# B7_OpenCR_PCB_Shield.net
KiCad netlist of a schematic drawn in EAGLE
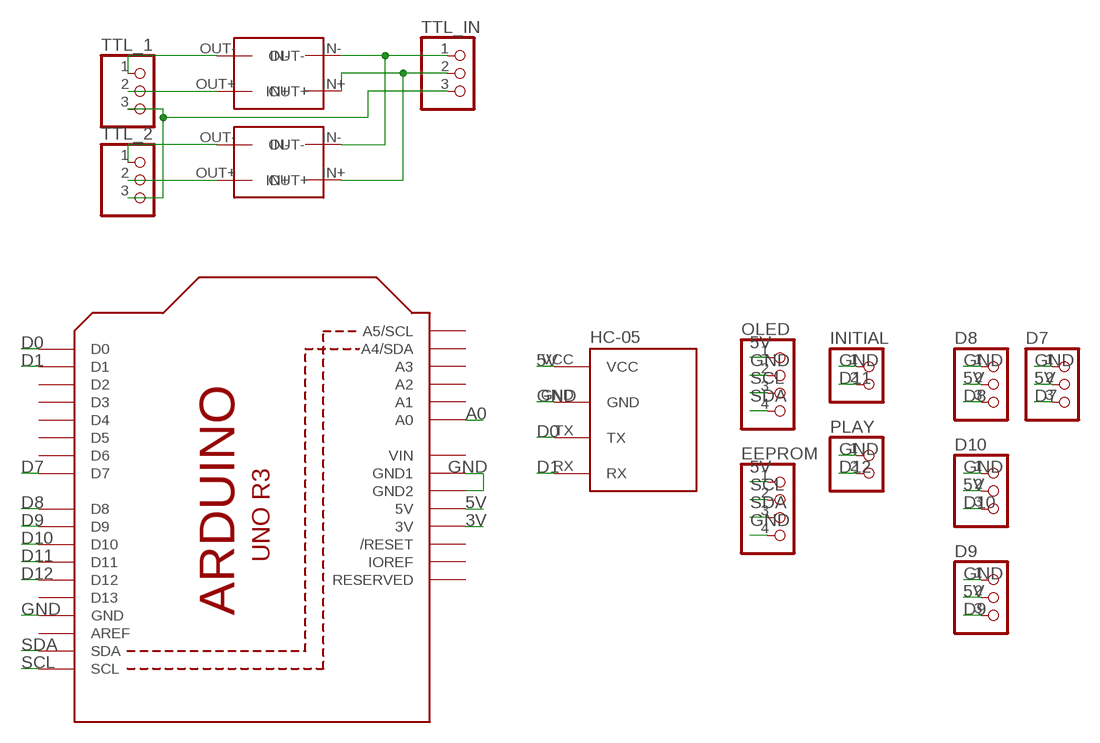
[diagram p0: schematic, sheet 1]

(export (version "E")
  (design (tool "Eeschema 10.0.6"))
  (components
    (comp (ref "D7")
      (value "PINHD-1X3")
      (footprint "eagle-import:1X03")
      (libsource (lib "eagle-import") (part "PINHD-1X3"))
    )
    (comp (ref "D8")
      (value "PINHD-1X3")
      (footprint "eagle-import:1X03")
      (libsource (lib "eagle-import") (part "PINHD-1X3"))
    )
    (comp (ref "D9")
      (value "PINHD-1X3")
      (footprint "eagle-import:1X03")
      (libsource (lib "eagle-import") (part "PINHD-1X3"))
    )
    (comp (ref "D10")
      (value "PINHD-1X3")
      (footprint "eagle-import:1X03")
      (libsource (lib "eagle-import") (part "PINHD-1X3"))
    )
    (comp (ref "EEPROM")
      (value "PINHD-1X4")
      (footprint "eagle-import:1X04")
      (libsource (lib "eagle-import") (part "PINHD-1X4"))
    )
    (comp (ref "HC-05")
      (value "BLUETOOTH_BOARD")
      (footprint "eagle-import:BT_BOARD_FOOTPRINT")
      (libsource (lib "eagle-import") (part "BLUETOOTH_BOARD"))
    )
    (comp (ref "INITIAL")
      (value "PINHD-1X2")
      (footprint "eagle-import:1X02")
      (libsource (lib "eagle-import") (part "PINHD-1X2"))
    )
    (comp (ref "OLED")
      (value "PINHD-1X4")
      (footprint "eagle-import:1X04")
      (libsource (lib "eagle-import") (part "PINHD-1X4"))
    )
    (comp (ref "PLAY")
      (value "PINHD-1X2")
      (footprint "eagle-import:1X02")
      (libsource (lib "eagle-import") (part "PINHD-1X2"))
    )
    (comp (ref "TTL_1")
      (value "PINHD-1X3")
      (footprint "eagle-import:1X03")
      (libsource (lib "eagle-import") (part "PINHD-1X3"))
    )
    (comp (ref "TTL_2")
      (value "PINHD-1X3")
      (footprint "eagle-import:1X03")
      (libsource (lib "eagle-import") (part "PINHD-1X3"))
    )
    (comp (ref "TTL_IN")
      (value "PINHD-1X3")
      (footprint "eagle-import:1X03")
      (libsource (lib "eagle-import") (part "PINHD-1X3"))
    )
    (comp (ref "U$1")
      (value "LM2596LM2596")
      (footprint "eagle-import:LM2596")
      (libsource (lib "eagle-import") (part "LM2596LM2596"))
    )
    (comp (ref "U$2")
      (value "LM2596LM2596")
      (footprint "eagle-import:LM2596")
      (libsource (lib "eagle-import") (part "LM2596LM2596"))
    )
    (comp (ref "U2")
      (value "ARDUINOR3-BPLACE")
      (footprint "eagle-import:ARDUINOR3-BPLACE")
      (libsource (lib "eagle-import") (part "ARDUINOR3-BPLACE"))
    )
  )
  (nets
    (net (code "1") (name "/3V") (class "Default")
      (node (ref "U2") (pin "3V") (pinfunction "3V_3V") (pintype "power_in"))
    )
    (net (code "2") (name "/5V") (class "Default")
      (node (ref "D10") (pin "2") (pinfunction "2_2") (pintype "passive"))
      (node (ref "D7") (pin "2") (pinfunction "2_2") (pintype "passive"))
      (node (ref "D8") (pin "2") (pinfunction "2_2") (pintype "passive"))
      (node (ref "D9") (pin "2") (pinfunction "2_2") (pintype "passive"))
      (node (ref "EEPROM") (pin "1") (pinfunction "1_1") (pintype "passive"))
      (node (ref "HC-05") (pin "VCC") (pinfunction "VCC_VCC") (pintype "bidirectional"))
      (node (ref "OLED") (pin "1") (pinfunction "1_1") (pintype "passive"))
      (node (ref "U2") (pin "5V") (pinfunction "5V_5V") (pintype "power_in"))
    )
    (net (code "3") (name "/A0") (class "Default")
      (node (ref "U2") (pin "A0") (pinfunction "A0_A0") (pintype "bidirectional"))
    )
    (net (code "4") (name "/D0") (class "Default")
      (node (ref "HC-05") (pin "TX") (pinfunction "TX_TX") (pintype "bidirectional"))
      (node (ref "U2") (pin "D0") (pinfunction "D0_D0") (pintype "bidirectional"))
    )
    (net (code "5") (name "/D1") (class "Default")
      (node (ref "HC-05") (pin "RX") (pinfunction "RX_RX") (pintype "bidirectional"))
      (node (ref "U2") (pin "D1") (pinfunction "D1_D1") (pintype "bidirectional"))
    )
    (net (code "6") (name "/D7") (class "Default")
      (node (ref "D7") (pin "3") (pinfunction "3_3") (pintype "passive"))
      (node (ref "U2") (pin "D7") (pinfunction "D7_D7") (pintype "bidirectional"))
    )
    (net (code "7") (name "/D8") (class "Default")
      (node (ref "D8") (pin "3") (pinfunction "3_3") (pintype "passive"))
      (node (ref "U2") (pin "D8") (pinfunction "D8_D8") (pintype "bidirectional"))
    )
    (net (code "8") (name "/D9") (class "Default")
      (node (ref "D9") (pin "3") (pinfunction "3_3") (pintype "passive"))
      (node (ref "U2") (pin "D9") (pinfunction "D9_D9") (pintype "bidirectional"))
    )
    (net (code "9") (name "/D10") (class "Default")
      (node (ref "D10") (pin "3") (pinfunction "3_3") (pintype "passive"))
      (node (ref "U2") (pin "D10") (pinfunction "D10_D10") (pintype "bidirectional"))
    )
    (net (code "10") (name "/D11") (class "Default")
      (node (ref "INITIAL") (pin "2") (pinfunction "2_2") (pintype "passive"))
      (node (ref "U2") (pin "D11") (pinfunction "D11_D11") (pintype "bidirectional"))
    )
    (net (code "11") (name "/D12") (class "Default")
      (node (ref "PLAY") (pin "2") (pinfunction "2_2") (pintype "passive"))
      (node (ref "U2") (pin "D12") (pinfunction "D12_D12") (pintype "bidirectional"))
    )
    (net (code "12") (name "/GND") (class "Default")
      (node (ref "D10") (pin "1") (pinfunction "1_1") (pintype "passive"))
      (node (ref "D7") (pin "1") (pinfunction "1_1") (pintype "passive"))
      (node (ref "D8") (pin "1") (pinfunction "1_1") (pintype "passive"))
      (node (ref "D9") (pin "1") (pinfunction "1_1") (pintype "passive"))
      (node (ref "EEPROM") (pin "4") (pinfunction "4_4") (pintype "passive"))
      (node (ref "HC-05") (pin "GND") (pinfunction "GND_GND") (pintype "bidirectional"))
      (node (ref "INITIAL") (pin "1") (pinfunction "1_1") (pintype "passive"))
      (node (ref "OLED") (pin "2") (pinfunction "2_2") (pintype "passive"))
      (node (ref "PLAY") (pin "1") (pinfunction "1_1") (pintype "passive"))
      (node (ref "U2") (pin "GND") (pinfunction "GND_GND") (pintype "power_in"))
      (node (ref "U2") (pin "GND1") (pinfunction "GND1_GND1") (pintype "power_in"))
      (node (ref "U2") (pin "GND2") (pinfunction "GND2_GND2") (pintype "power_in"))
    )
    (net (code "13") (name "/SCL") (class "Default")
      (node (ref "EEPROM") (pin "2") (pinfunction "2_2") (pintype "passive"))
      (node (ref "OLED") (pin "3") (pinfunction "3_3") (pintype "passive"))
      (node (ref "U2") (pin "SCL") (pinfunction "SCL_SCL") (pintype "bidirectional"))
    )
    (net (code "14") (name "/SDA") (class "Default")
      (node (ref "EEPROM") (pin "3") (pinfunction "3_3") (pintype "passive"))
      (node (ref "OLED") (pin "4") (pinfunction "4_4") (pintype "passive"))
      (node (ref "U2") (pin "SDA") (pinfunction "SDA_SDA") (pintype "bidirectional"))
    )
    (net (code "15") (name "/VIN") (class "Default")
      (node (ref "U2") (pin "VIN") (pinfunction "VIN_VIN") (pintype "power_in"))
    )
    (net (code "16") (name "Net-(TTL_1-Pad1)") (class "Default")
      (node (ref "TTL_1") (pin "1") (pinfunction "1_1") (pintype "passive"))
      (node (ref "U$1") (pin "OUT-") (pinfunction "OUT-_OUT-") (pintype "bidirectional"))
    )
    (net (code "17") (name "Net-(TTL_1-Pad2)") (class "Default")
      (node (ref "TTL_1") (pin "2") (pinfunction "2_2") (pintype "passive"))
      (node (ref "U$1") (pin "OUT+") (pinfunction "OUT+_OUT+") (pintype "bidirectional"))
    )
    (net (code "18") (name "Net-(TTL_1-Pad3)") (class "Default")
      (node (ref "TTL_1") (pin "3") (pinfunction "3_3") (pintype "passive"))
      (node (ref "TTL_2") (pin "3") (pinfunction "3_3") (pintype "passive"))
      (node (ref "TTL_IN") (pin "3") (pinfunction "3_3") (pintype "passive"))
    )
    (net (code "19") (name "Net-(TTL_2-Pad1)") (class "Default")
      (node (ref "TTL_2") (pin "1") (pinfunction "1_1") (pintype "passive"))
      (node (ref "U$2") (pin "OUT-") (pinfunction "OUT-_OUT-") (pintype "bidirectional"))
    )
    (net (code "20") (name "Net-(TTL_2-Pad2)") (class "Default")
      (node (ref "TTL_2") (pin "2") (pinfunction "2_2") (pintype "passive"))
      (node (ref "U$2") (pin "OUT+") (pinfunction "OUT+_OUT+") (pintype "bidirectional"))
    )
    (net (code "21") (name "Net-(TTL_IN-Pad1)") (class "Default")
      (node (ref "TTL_IN") (pin "1") (pinfunction "1_1") (pintype "passive"))
      (node (ref "U$1") (pin "IN-") (pinfunction "IN-_IN-") (pintype "bidirectional"))
      (node (ref "U$2") (pin "IN-") (pinfunction "IN-_IN-") (pintype "bidirectional"))
    )
    (net (code "22") (name "Net-(TTL_IN-Pad2)") (class "Default")
      (node (ref "TTL_IN") (pin "2") (pinfunction "2_2") (pintype "passive"))
      (node (ref "U$1") (pin "IN+") (pinfunction "IN+_IN+") (pintype "bidirectional"))
      (node (ref "U$2") (pin "IN+") (pinfunction "IN+_IN+") (pintype "bidirectional"))
    )
    (net (code "23") (name "unconnected-(U2-A4{slash}SDA-PadA4)") (class "Default")
      (node (ref "U2") (pin "A4") (pinfunction "A4/SDA_A4") (pintype "bidirectional"))
    )
    (net (code "24") (name "unconnected-(U2-A5{slash}SCL-PadA5)") (class "Default")
      (node (ref "U2") (pin "A5") (pinfunction "A5/SCL_A5") (pintype "bidirectional"))
    )
    (net (code "25") (name "unconnected-(U2-PadA1)") (class "Default")
      (node (ref "U2") (pin "A1") (pinfunction "A1_A1") (pintype "bidirectional"))
    )
    (net (code "26") (name "unconnected-(U2-PadA2)") (class "Default")
      (node (ref "U2") (pin "A2") (pinfunction "A2_A2") (pintype "bidirectional"))
    )
    (net (code "27") (name "unconnected-(U2-PadA3)") (class "Default")
      (node (ref "U2") (pin "A3") (pinfunction "A3_A3") (pintype "bidirectional"))
    )
    (net (code "28") (name "unconnected-(U2-PadAREF)") (class "Default")
      (node (ref "U2") (pin "AREF") (pinfunction "AREF_AREF") (pintype "bidirectional"))
    )
    (net (code "29") (name "unconnected-(U2-PadD2)") (class "Default")
      (node (ref "U2") (pin "D2") (pinfunction "D2_D2") (pintype "bidirectional"))
    )
    (net (code "30") (name "unconnected-(U2-PadD3)") (class "Default")
      (node (ref "U2") (pin "D3") (pinfunction "D3_D3") (pintype "bidirectional"))
    )
    (net (code "31") (name "unconnected-(U2-PadD4)") (class "Default")
      (node (ref "U2") (pin "D4") (pinfunction "D4_D4") (pintype "bidirectional"))
    )
    (net (code "32") (name "unconnected-(U2-PadD5)") (class "Default")
      (node (ref "U2") (pin "D5") (pinfunction "D5_D5") (pintype "bidirectional"))
    )
    (net (code "33") (name "unconnected-(U2-PadD6)") (class "Default")
      (node (ref "U2") (pin "D6") (pinfunction "D6_D6") (pintype "bidirectional"))
    )
    (net (code "34") (name "unconnected-(U2-PadD13)") (class "Default")
      (node (ref "U2") (pin "D13") (pinfunction "D13_D13") (pintype "bidirectional"))
    )
    (net (code "35") (name "unconnected-(U2-PadIOREF)") (class "Default")
      (node (ref "U2") (pin "IOREF") (pinfunction "IOREF_IOREF") (pintype "output"))
    )
    (net (code "36") (name "unconnected-(U2-PadRESERVED)") (class "Default")
      (node (ref "U2") (pin "RESERVED") (pinfunction "RESERVED_RESERVED") (pintype "no_connect"))
    )
    (net (code "37") (name "unconnected-(U2-{slash}RESET-PadRESET)") (class "Default")
      (node (ref "U2") (pin "RESET") (pinfunction "/RESET_RESET") (pintype "bidirectional"))
    )
  )
)
